# MCU_-_MKL05VQFN24.net
KiCad netlist of a schematic drawn in Altium Designer
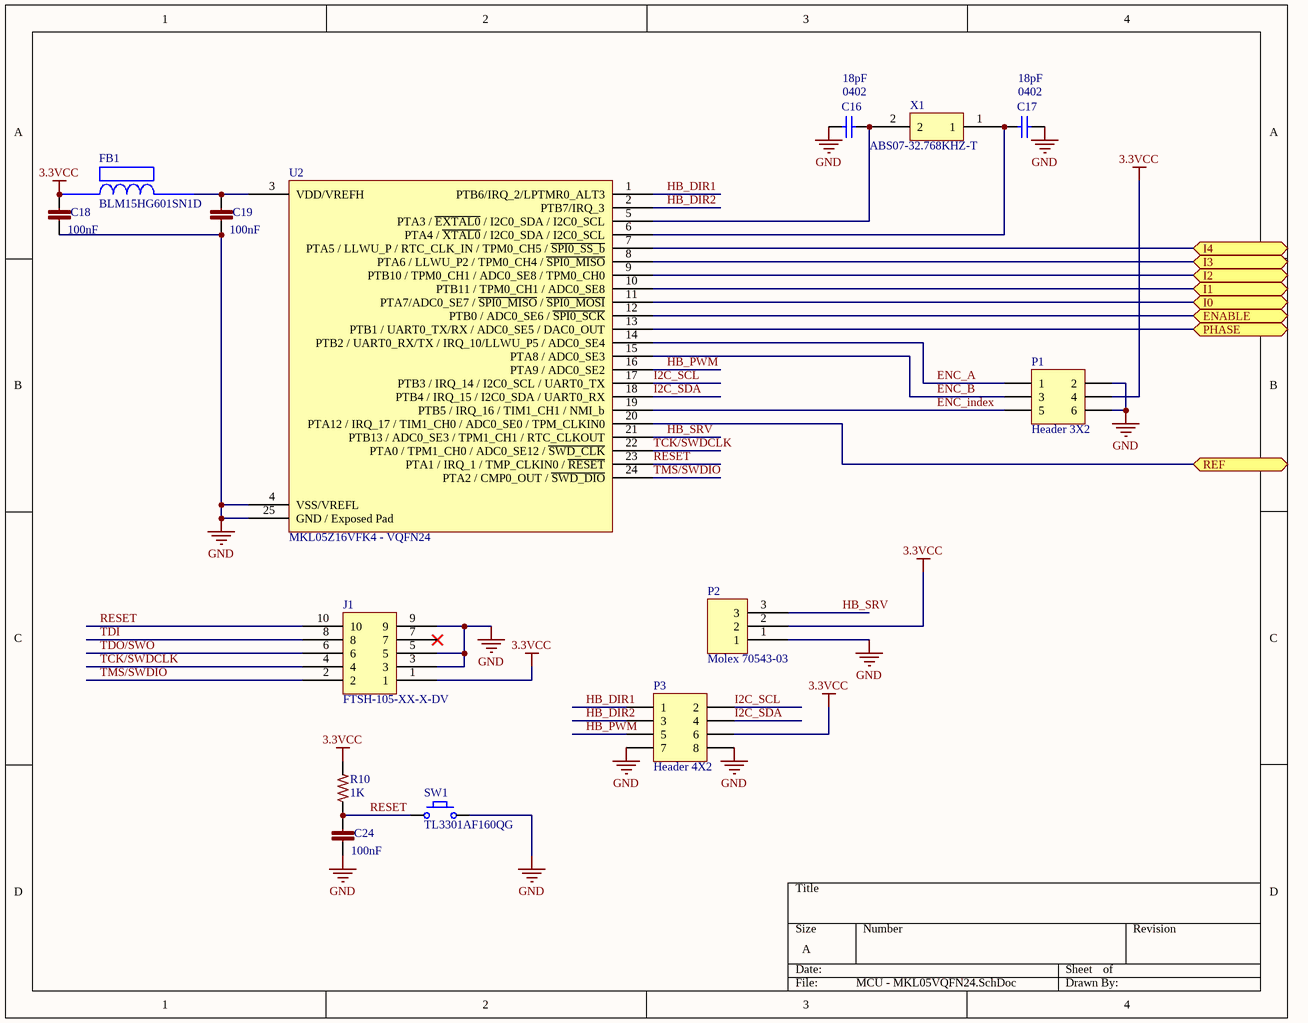
[diagram p0: MCU - MKL05VQFN24.SchDoc]

(export (version "E")
  (design (tool "Eeschema 10.0.6"))
  (components
    (comp (ref "C16")
      (value "0402")
      (footprint "C0402")
      (description "CAP CER 18PF 50V 2% NP0 0402")
      (fields
        (field (name "MANUFACTURE PART #") "CL05C180GB5NNNC")
        (field (name "MANUFACTURER") "Samsung")
        (field (name "ALTIUM_VALUE") "18pF")
        (field (name "PUBLISHER") "Ultimachine")
      )
      (libsource (lib "Tigershark3D") (part "CL05C180GB5NNNC"))
    )
    (comp (ref "C17")
      (value "0402")
      (footprint "C0402")
      (description "CAP CER 18PF 50V 2% NP0 0402")
      (fields
        (field (name "MANUFACTURE PART #") "CL05C180GB5NNNC")
        (field (name "MANUFACTURER") "Samsung")
        (field (name "ALTIUM_VALUE") "18pF")
        (field (name "PUBLISHER") "Ultimachine")
      )
      (libsource (lib "Tigershark3D") (part "CL05C180GB5NNNC"))
    )
    (comp (ref "C18")
      (value "100nF")
      (footprint "C0402")
      (description "CAP CER 0402 100nF 16V 10% X7R")
      (fields
        (field (name "MANUFACTURERPARTNUMBER") "GRM155R71C104KA88D")
        (field (name "PUBLISHER") "UltiMachine")
      )
      (libsource (lib "3Delight") (part "GRM155R71C104KA88D"))
    )
    (comp (ref "C19")
      (value "100nF")
      (footprint "C0402")
      (description "CAP CER 0402 100nF 16V 10% X7R")
      (fields
        (field (name "MANUFACTURERPARTNUMBER") "GRM155R71C104KA88D")
        (field (name "PUBLISHER") "UltiMachine")
      )
      (libsource (lib "3Delight") (part "GRM155R71C104KA88D"))
    )
    (comp (ref "C24")
      (value "100nF")
      (footprint "C0402")
      (description "CAP CER 0402 100nF 16V 10% X7R")
      (fields
        (field (name "MANUFACTURERPARTNUMBER") "GRM155R71C104KA88D")
        (field (name "PUBLISHER") "UltiMachine")
      )
      (libsource (lib "3Delight") (part "GRM155R71C104KA88D"))
    )
    (comp (ref "FB1")
      (value "BLM15HG601SN1D")
      (footprint "BLM18PG121SN1D")
      (libsource (lib "AHD Part Library") (part "BLM15HG601SN1D"))
    )
    (comp (ref "J1")
      (value "FTSH-105-XX-X-DV")
      (footprint "FTSH-105-XX-X-DV")
      (libsource (lib "Adams Altium Library") (part "ARM Cortex JTAG-DEBUG Header"))
    )
    (comp (ref "P1")
      (value "Header 3X2")
      (footprint "HDR2X3 Shrouded - Molex 0901301106")
      (description "Header, 3-Pin, Dual row")
      (fields (field (name "PUBLISHER") "Altium Limited"))
      (libsource (lib "Miscellaneous Connectors") (part "Header 3X2"))
    )
    (comp (ref "P2")
      (value "Molex 70543-03")
      (footprint "70543-03")
      (libsource (lib "RADMBo Schematic Library") (part "Molex Endstop"))
    )
    (comp (ref "P3")
      (value "Header 4X2")
      (footprint "HDR2X4 Shrouded")
      (description "Header, 4-Pin, Dual row")
      (fields (field (name "PUBLISHER") "Altium Limited"))
      (libsource (lib "Miscellaneous Connectors") (part "Header 4X2"))
    )
    (comp (ref "R10")
      (value "1K")
      (footprint "R0603")
      (description "RES 0603 1K 100mW 1%")
      (fields
        (field (name "MANUFACTURERPARTNUMBER") "ERJ-3EKF1001V")
        (field (name "PUBLISHER") "UltiMachine")
      )
      (libsource (lib "3Delight") (part "ERJ-3EKF1001V"))
    )
    (comp (ref "SW1")
      (value "TL3301AF160QG")
      (footprint "TL3301AF160QG")
      (libsource (lib "MongoosMini") (part "TL3301AF160QG"))
    )
    (comp (ref "U2")
      (value "MKL05Z16VFK4 - VQFN24")
      (footprint "98ASA00474D")
      (description "ARM Cortex M0+")
      (libsource (lib "Encoder Fin") (part "MKL05Z16VFK4 - 24 Pin VQFN"))
    )
    (comp (ref "X1")
      (value "ABS07-32.768KHZ-T")
      (footprint "ABS07-32.768KHZ-T")
      (description "ABS07-32.768KHZ-T RTC Crystal Oscillator")
      (libsource (lib "Adams Altium Library") (part "ABS07-32.768KHZ-T"))
    )
  )
  (nets
    (net (code "1") (name "/ENABLE") (class "Default")
      (node (ref "U2") (pin "12") (pinfunction "PTB0_/_ADC0_SE6_/_~{SPI0_SCK}_12") (pintype "passive"))
    )
    (net (code "2") (name "/ENC_A") (class "Default")
      (node (ref "P1") (pin "1") (pinfunction "1_1") (pintype "passive"))
      (node (ref "U2") (pin "14") (pinfunction "PTB2_/_UART0_RX/TX_/_IRQ_10/LLWU_P5_/_ADC0_SE4_14") (pintype "passive"))
    )
    (net (code "3") (name "/ENC_B") (class "Default")
      (node (ref "P1") (pin "3") (pinfunction "3_3") (pintype "passive"))
      (node (ref "U2") (pin "15") (pinfunction "PTA8_/_ADC0_SE3_15") (pintype "passive"))
    )
    (net (code "4") (name "/ENC_index") (class "Default")
      (node (ref "P1") (pin "5") (pinfunction "5_5") (pintype "passive"))
      (node (ref "U2") (pin "19") (pinfunction "PTB5_/_IRQ_16_/_TIM1_CH1_/_NMI_b_19") (pintype "passive"))
    )
    (net (code "5") (name "/HB_DIR1") (class "Default")
      (node (ref "P3") (pin "1") (pinfunction "1_1") (pintype "passive"))
      (node (ref "U2") (pin "1") (pinfunction "PTB6/IRQ_2/LPTMR0_ALT3_1") (pintype "passive"))
    )
    (net (code "6") (name "/HB_DIR2") (class "Default")
      (node (ref "P3") (pin "3") (pinfunction "3_3") (pintype "passive"))
      (node (ref "U2") (pin "2") (pinfunction "PTB7/IRQ_3_2") (pintype "passive"))
    )
    (net (code "7") (name "/HB_PWM") (class "Default")
      (node (ref "P3") (pin "5") (pinfunction "5_5") (pintype "passive"))
      (node (ref "U2") (pin "16") (pinfunction "PTA9_/_ADC0_SE2_16") (pintype "passive"))
    )
    (net (code "8") (name "/HB_SRV") (class "Default")
      (node (ref "P2") (pin "3") (pinfunction "3_3") (pintype "passive"))
      (node (ref "U2") (pin "21") (pinfunction "PTB13_/_ADC0_SE3_/_TPM1_CH1_/_RTC_CLKOUT_21") (pintype "passive"))
    )
    (net (code "9") (name "/I0") (class "Default")
      (node (ref "U2") (pin "11") (pinfunction "PTA7/ADC0_SE7_/_~{SPI0_MISO}_/_~{SPI0_MOSI}_11") (pintype "passive"))
    )
    (net (code "10") (name "/I1") (class "Default")
      (node (ref "U2") (pin "10") (pinfunction "PTB11_/_TPM0_CH1_/_ADC0_SE8_10") (pintype "passive"))
    )
    (net (code "11") (name "/I2") (class "Default")
      (node (ref "U2") (pin "9") (pinfunction "PTB10_/_TPM0_CH1_/_ADC0_SE8_/_TPM0_CH0_9") (pintype "passive"))
    )
    (net (code "12") (name "/I2C_SCL") (class "Default")
      (node (ref "P3") (pin "2") (pinfunction "2_2") (pintype "passive"))
      (node (ref "U2") (pin "17") (pinfunction "PTB3_/_IRQ_14_/_I2C0_SCL_/_UART0_TX_17") (pintype "passive"))
    )
    (net (code "13") (name "/I2C_SDA") (class "Default")
      (node (ref "P3") (pin "4") (pinfunction "4_4") (pintype "passive"))
      (node (ref "U2") (pin "18") (pinfunction "PTB4_/_IRQ_15_/_I2C0_SDA_/_UART0_RX_18") (pintype "passive"))
    )
    (net (code "14") (name "/I3") (class "Default")
      (node (ref "U2") (pin "8") (pinfunction "PTA6_/_LLWU_P2_/_TPM0_CH4_/_~{SPI0_MISO}_8") (pintype "passive"))
    )
    (net (code "15") (name "/I4") (class "Default")
      (node (ref "U2") (pin "7") (pinfunction "PTA5_/_LLWU_P_/_RTC_CLK_IN_/_TPM0_CH5_/_~{SPI0_SS_b}_7") (pintype "passive"))
    )
    (net (code "16") (name "/PHASE") (class "Default")
      (node (ref "U2") (pin "13") (pinfunction "PTB1_/_UART0_TX/RX_/_ADC0_SE5_/_DAC0_OUT_13") (pintype "passive"))
    )
    (net (code "17") (name "/REF") (class "Default")
      (node (ref "U2") (pin "20") (pinfunction "PTA12_/_IRQ_17_/_TIM1_CH0_/_ADC0_SE0_/_TPM_CLKIN0_20") (pintype "passive"))
    )
    (net (code "18") (name "/RESET") (class "Default")
      (node (ref "C24") (pin "1") (pinfunction "1_1") (pintype "passive"))
      (node (ref "J1") (pin "10") (pinfunction "10_10") (pintype "passive"))
      (node (ref "R10") (pin "1") (pinfunction "1_1") (pintype "passive"))
      (node (ref "SW1") (pin "1") (pintype "passive"))
      (node (ref "U2") (pin "23") (pinfunction "PTA1_/_IRQ_1_/_TMP_CLKIN0_/_~{RESET}_23") (pintype "passive"))
    )
    (net (code "19") (name "/TCK{slash}SWDCLK") (class "Default")
      (node (ref "J1") (pin "4") (pinfunction "4_4") (pintype "passive"))
      (node (ref "U2") (pin "22") (pinfunction "PTA0_/_TPM1_CH0_/_ADC0_SE12_/_~{SWD_CLK}_22") (pintype "passive"))
    )
    (net (code "20") (name "/TDI") (class "Default")
      (node (ref "J1") (pin "8") (pinfunction "8_8") (pintype "passive"))
    )
    (net (code "21") (name "/TDO{slash}SWO") (class "Default")
      (node (ref "J1") (pin "6") (pinfunction "6_6") (pintype "passive"))
    )
    (net (code "22") (name "/TMS{slash}SWDIO") (class "Default")
      (node (ref "J1") (pin "2") (pinfunction "2_2") (pintype "passive"))
      (node (ref "U2") (pin "24") (pinfunction "PTA2_/_CMP0_OUT_/_~{SWD_DIO}_24") (pintype "passive"))
    )
    (net (code "23") (name "3.3VCC") (class "Default")
      (node (ref "C18") (pin "1") (pinfunction "1_1") (pintype "passive"))
      (node (ref "FB1") (pin "1") (pinfunction "1_1") (pintype "passive"))
      (node (ref "J1") (pin "1") (pinfunction "1_1") (pintype "passive"))
      (node (ref "P1") (pin "4") (pinfunction "4_4") (pintype "passive"))
      (node (ref "P2") (pin "2") (pinfunction "2_2") (pintype "passive"))
      (node (ref "P3") (pin "6") (pinfunction "6_6") (pintype "passive"))
      (node (ref "R10") (pin "2") (pinfunction "2_2") (pintype "passive"))
    )
    (net (code "24") (name "GND") (class "Default")
      (node (ref "C16") (pin "2") (pinfunction "2_2") (pintype "passive"))
      (node (ref "C17") (pin "1") (pinfunction "1_1") (pintype "passive"))
      (node (ref "C18") (pin "2") (pinfunction "2_2") (pintype "passive"))
      (node (ref "C19") (pin "2") (pinfunction "2_2") (pintype "passive"))
      (node (ref "C24") (pin "2") (pinfunction "2_2") (pintype "passive"))
      (node (ref "J1") (pin "3") (pinfunction "3_3") (pintype "passive"))
      (node (ref "J1") (pin "5") (pinfunction "5_5") (pintype "passive"))
      (node (ref "J1") (pin "9") (pinfunction "9_9") (pintype "passive"))
      (node (ref "P1") (pin "2") (pinfunction "2_2") (pintype "passive"))
      (node (ref "P1") (pin "6") (pinfunction "6_6") (pintype "passive"))
      (node (ref "P2") (pin "1") (pinfunction "1_1") (pintype "passive"))
      (node (ref "P3") (pin "7") (pinfunction "7_7") (pintype "passive"))
      (node (ref "P3") (pin "8") (pinfunction "8_8") (pintype "passive"))
      (node (ref "SW1") (pin "2") (pintype "passive"))
      (node (ref "U2") (pin "25") (pinfunction "GND_/_Exposed_Pad_25") (pintype "passive"))
      (node (ref "U2") (pin "4") (pinfunction "VSS/VREFL_4") (pintype "passive"))
    )
    (net (code "25") (name "Net-(U2-PTA3_{slash}_~{EXTAL0}_{slash}_I2C0_SDA_{slash}_I2C0_SCL)") (class "Default")
      (node (ref "C16") (pin "1") (pinfunction "1_1") (pintype "passive"))
      (node (ref "U2") (pin "5") (pinfunction "PTA3_/_~{EXTAL0}_/_I2C0_SDA_/_I2C0_SCL_5") (pintype "passive"))
      (node (ref "X1") (pin "2") (pinfunction "2_2") (pintype "passive"))
    )
    (net (code "26") (name "Net-(U2-PTA4_{slash}_~{XTAL0}_{slash}_I2C0_SDA_{slash}_I2C0_SCL)") (class "Default")
      (node (ref "C17") (pin "2") (pinfunction "2_2") (pintype "passive"))
      (node (ref "U2") (pin "6") (pinfunction "PTA4_/_~{XTAL0}_/_I2C0_SDA_/_I2C0_SCL_6") (pintype "passive"))
      (node (ref "X1") (pin "1") (pinfunction "1_1") (pintype "passive"))
    )
    (net (code "27") (name "Net-(U2-VDD{slash}VREFH)") (class "Default")
      (node (ref "C19") (pin "1") (pinfunction "1_1") (pintype "passive"))
      (node (ref "FB1") (pin "2") (pinfunction "2_2") (pintype "passive"))
      (node (ref "U2") (pin "3") (pinfunction "VDD/VREFH_3") (pintype "passive"))
    )
    (net (code "28") (name "unconnected-(J1-Pad7)") (class "Default")
      (node (ref "J1") (pin "7") (pinfunction "7_7") (pintype "passive+no_connect"))
    )
  )
)
